# MPR121-Breakout-v12.net
KiCad netlist of a schematic drawn in EAGLE
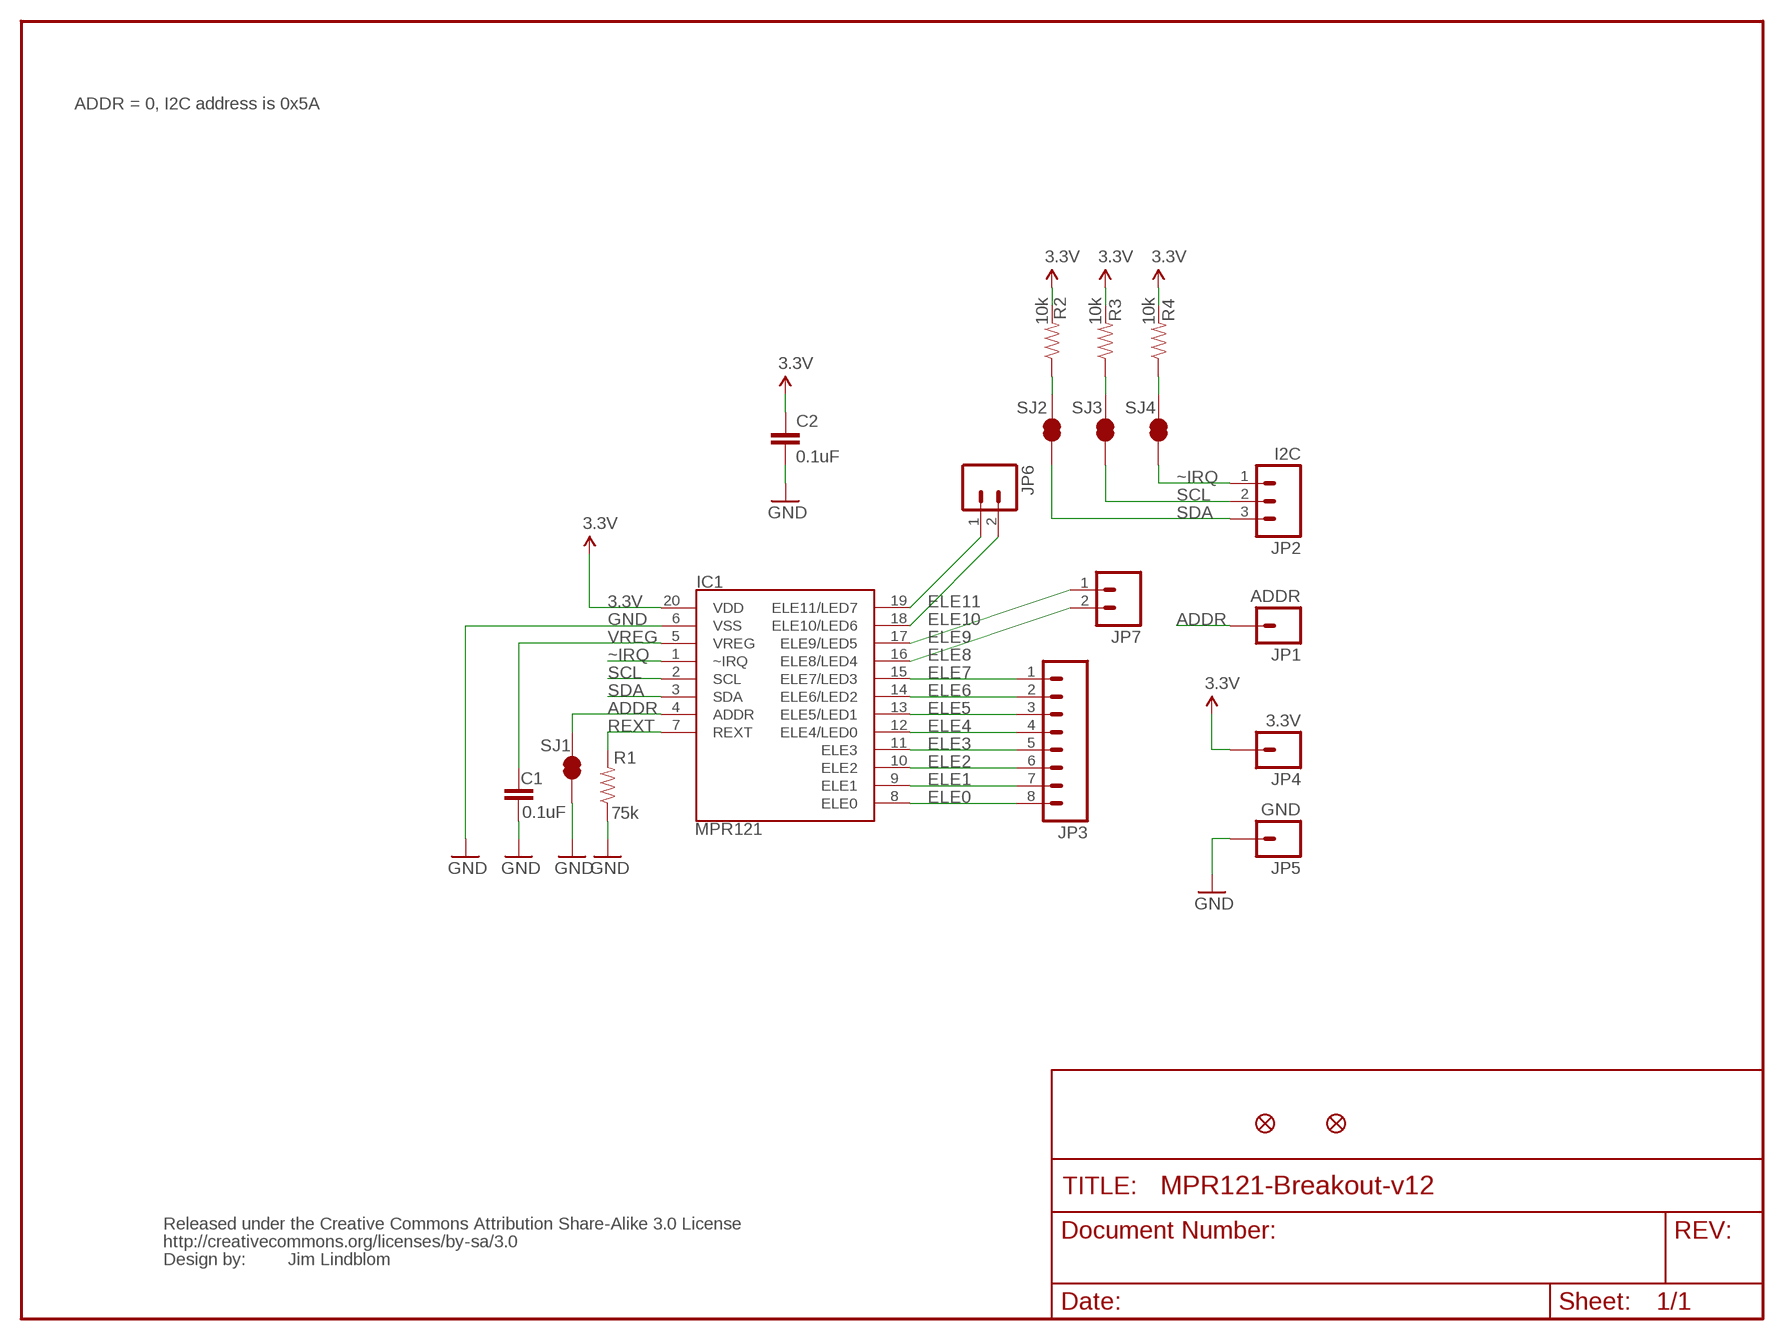
[diagram p0: schematic, sheet 1]

(export (version "E")
  (design (tool "Eeschema 10.0.6"))
  (components
    (comp (ref "C1")
      (value "0.1uF")
      (footprint "eagle-import:0603-CAP")
      (libsource (lib "eagle-import") (part "CAP0603-CAP"))
    )
    (comp (ref "C2")
      (value "0.1uF")
      (footprint "eagle-import:0603-CAP")
      (libsource (lib "eagle-import") (part "CAP0603-CAP"))
    )
    (comp (ref "IC1")
      (value "MPR121")
      (footprint "eagle-import:QFN-20-0.4MM")
      (libsource (lib "eagle-import") (part "MPR121QFN20"))
    )
    (comp (ref "JP1")
      (value "ADDR")
      (footprint "eagle-import:1X01")
      (libsource (lib "eagle-import") (part "M01PTH"))
    )
    (comp (ref "JP2")
      (value "I2C")
      (footprint "eagle-import:1X03")
      (libsource (lib "eagle-import") (part "M03PTH"))
    )
    (comp (ref "JP3")
      (value "M081X08")
      (footprint "eagle-import:1X08")
      (libsource (lib "eagle-import") (part "M081X08"))
    )
    (comp (ref "JP4")
      (value "3.3V")
      (footprint "eagle-import:1X01")
      (libsource (lib "eagle-import") (part "M01PTH"))
    )
    (comp (ref "JP5")
      (value "GND")
      (footprint "eagle-import:1X01")
      (libsource (lib "eagle-import") (part "M01PTH"))
    )
    (comp (ref "JP6")
      (value "M02LOCK")
      (footprint "eagle-import:1X02_LOCK")
      (libsource (lib "eagle-import") (part "M02LOCK"))
    )
    (comp (ref "JP7")
      (value "M02LOCK")
      (footprint "eagle-import:1X02_LOCK")
      (libsource (lib "eagle-import") (part "M02LOCK"))
    )
    (comp (ref "JP8")
      (value "FIDUCIAL1X2")
      (footprint "eagle-import:FIDUCIAL-1X2")
      (libsource (lib "eagle-import") (part "FIDUCIAL1X2"))
    )
    (comp (ref "JP9")
      (value "FIDUCIAL1X2")
      (footprint "eagle-import:FIDUCIAL-1X2")
      (libsource (lib "eagle-import") (part "FIDUCIAL1X2"))
    )
    (comp (ref "R1")
      (value "75k")
      (footprint "eagle-import:0603-RES")
      (libsource (lib "eagle-import") (part "RESISTOR0603-RES"))
    )
    (comp (ref "R2")
      (value "10k")
      (footprint "eagle-import:0603-RES")
      (libsource (lib "eagle-import") (part "RESISTOR0603-RES"))
    )
    (comp (ref "R3")
      (value "10k")
      (footprint "eagle-import:0603-RES")
      (libsource (lib "eagle-import") (part "RESISTOR0603-RES"))
    )
    (comp (ref "R4")
      (value "10k")
      (footprint "eagle-import:0603-RES")
      (libsource (lib "eagle-import") (part "RESISTOR0603-RES"))
    )
    (comp (ref "SJ1")
      (value "SOLDERJUMPERNO")
      (footprint "eagle-import:SJ_2S-NO")
      (libsource (lib "eagle-import") (part "SOLDERJUMPERNO"))
    )
    (comp (ref "SJ2")
      (value "SOLDERJUMPERNO")
      (footprint "eagle-import:SJ_2S-NO")
      (libsource (lib "eagle-import") (part "SOLDERJUMPERNO"))
    )
    (comp (ref "SJ3")
      (value "SOLDERJUMPERNO")
      (footprint "eagle-import:SJ_2S-NO")
      (libsource (lib "eagle-import") (part "SOLDERJUMPERNO"))
    )
    (comp (ref "SJ4")
      (value "SOLDERJUMPERNO")
      (footprint "eagle-import:SJ_2S-NO")
      (libsource (lib "eagle-import") (part "SOLDERJUMPERNO"))
    )
    (comp (ref "U$1")
      (value "CREATIVE_COMMONS")
      (footprint "eagle-import:CREATIVE_COMMONS")
      (libsource (lib "eagle-import") (part "CREATIVE_COMMONS"))
    )
  )
  (nets
    (net (code "1") (name "/ADDR") (class "Default")
      (node (ref "IC1") (pin "4") (pinfunction "ADDR_4") (pintype "bidirectional"))
      (node (ref "JP1") (pin "1") (pinfunction "1_1") (pintype "passive"))
      (node (ref "SJ1") (pin "2") (pinfunction "2_2") (pintype "passive"))
    )
    (net (code "2") (name "/ELE0") (class "Default")
      (node (ref "IC1") (pin "8") (pinfunction "ELE0_8") (pintype "bidirectional"))
      (node (ref "JP3") (pin "8") (pinfunction "8_8") (pintype "passive"))
    )
    (net (code "3") (name "/ELE1") (class "Default")
      (node (ref "IC1") (pin "9") (pinfunction "ELE1_9") (pintype "bidirectional"))
      (node (ref "JP3") (pin "7") (pinfunction "7_7") (pintype "passive"))
    )
    (net (code "4") (name "/ELE2") (class "Default")
      (node (ref "IC1") (pin "10") (pinfunction "ELE2_10") (pintype "bidirectional"))
      (node (ref "JP3") (pin "6") (pinfunction "6_6") (pintype "passive"))
    )
    (net (code "5") (name "/ELE3") (class "Default")
      (node (ref "IC1") (pin "11") (pinfunction "ELE3_11") (pintype "bidirectional"))
      (node (ref "JP3") (pin "5") (pinfunction "5_5") (pintype "passive"))
    )
    (net (code "6") (name "/ELE4") (class "Default")
      (node (ref "IC1") (pin "12") (pinfunction "ELE4/LED0_12") (pintype "bidirectional"))
      (node (ref "JP3") (pin "4") (pinfunction "4_4") (pintype "passive"))
    )
    (net (code "7") (name "/ELE5") (class "Default")
      (node (ref "IC1") (pin "13") (pinfunction "ELE5/LED1_13") (pintype "bidirectional"))
      (node (ref "JP3") (pin "3") (pinfunction "3_3") (pintype "passive"))
    )
    (net (code "8") (name "/ELE6") (class "Default")
      (node (ref "IC1") (pin "14") (pinfunction "ELE6/LED2_14") (pintype "bidirectional"))
      (node (ref "JP3") (pin "2") (pinfunction "2_2") (pintype "passive"))
    )
    (net (code "9") (name "/ELE7") (class "Default")
      (node (ref "IC1") (pin "15") (pinfunction "ELE7/LED3_15") (pintype "bidirectional"))
      (node (ref "JP3") (pin "1") (pinfunction "1_1") (pintype "passive"))
    )
    (net (code "10") (name "/ELE8") (class "Default")
      (node (ref "IC1") (pin "16") (pinfunction "ELE8/LED4_16") (pintype "bidirectional"))
      (node (ref "JP7") (pin "2") (pinfunction "2_2") (pintype "passive"))
    )
    (net (code "11") (name "/ELE9") (class "Default")
      (node (ref "IC1") (pin "17") (pinfunction "ELE9/LED5_17") (pintype "bidirectional"))
      (node (ref "JP7") (pin "1") (pinfunction "1_1") (pintype "passive"))
    )
    (net (code "12") (name "/ELE10") (class "Default")
      (node (ref "IC1") (pin "18") (pinfunction "ELE10/LED6_18") (pintype "bidirectional"))
      (node (ref "JP6") (pin "2") (pinfunction "2_2") (pintype "passive"))
    )
    (net (code "13") (name "/ELE11") (class "Default")
      (node (ref "IC1") (pin "19") (pinfunction "ELE11/LED7_19") (pintype "bidirectional"))
      (node (ref "JP6") (pin "1") (pinfunction "1_1") (pintype "passive"))
    )
    (net (code "14") (name "/REXT") (class "Default")
      (node (ref "IC1") (pin "7") (pinfunction "REXT_7") (pintype "bidirectional"))
      (node (ref "R1") (pin "2") (pinfunction "2_2") (pintype "passive"))
    )
    (net (code "15") (name "/SCL") (class "Default")
      (node (ref "IC1") (pin "2") (pinfunction "SCL_2") (pintype "bidirectional"))
      (node (ref "JP2") (pin "2") (pinfunction "2_2") (pintype "passive"))
      (node (ref "SJ3") (pin "1") (pinfunction "1_1") (pintype "passive"))
    )
    (net (code "16") (name "/SDA") (class "Default")
      (node (ref "IC1") (pin "3") (pinfunction "SDA_3") (pintype "bidirectional"))
      (node (ref "JP2") (pin "3") (pinfunction "3_3") (pintype "passive"))
      (node (ref "SJ2") (pin "1") (pinfunction "1_1") (pintype "passive"))
    )
    (net (code "17") (name "/VREG") (class "Default")
      (node (ref "C1") (pin "1") (pinfunction "1_1") (pintype "passive"))
      (node (ref "IC1") (pin "5") (pinfunction "VREG_5") (pintype "bidirectional"))
    )
    (net (code "18") (name "/~{IRQ}") (class "Default")
      (node (ref "IC1") (pin "1") (pinfunction "~{IRQ}_1") (pintype "bidirectional"))
      (node (ref "JP2") (pin "1") (pinfunction "1_1") (pintype "passive"))
      (node (ref "SJ4") (pin "1") (pinfunction "1_1") (pintype "passive"))
    )
    (net (code "19") (name "3.3V") (class "Default")
      (node (ref "C2") (pin "1") (pinfunction "1_1") (pintype "passive"))
      (node (ref "IC1") (pin "20") (pinfunction "VDD_20") (pintype "bidirectional"))
      (node (ref "JP4") (pin "1") (pinfunction "1_1") (pintype "passive"))
      (node (ref "R2") (pin "2") (pinfunction "2_2") (pintype "passive"))
      (node (ref "R3") (pin "2") (pinfunction "2_2") (pintype "passive"))
      (node (ref "R4") (pin "2") (pinfunction "2_2") (pintype "passive"))
    )
    (net (code "20") (name "GND") (class "Default")
      (node (ref "C1") (pin "2") (pinfunction "2_2") (pintype "passive"))
      (node (ref "C2") (pin "2") (pinfunction "2_2") (pintype "passive"))
      (node (ref "IC1") (pin "6") (pinfunction "VSS_6") (pintype "bidirectional"))
      (node (ref "JP5") (pin "1") (pinfunction "1_1") (pintype "passive"))
      (node (ref "R1") (pin "1") (pinfunction "1_1") (pintype "passive"))
      (node (ref "SJ1") (pin "1") (pinfunction "1_1") (pintype "passive"))
    )
    (net (code "21") (name "Net-(R2-Pad1)") (class "Default")
      (node (ref "R2") (pin "1") (pinfunction "1_1") (pintype "passive"))
      (node (ref "SJ2") (pin "2") (pinfunction "2_2") (pintype "passive"))
    )
    (net (code "22") (name "Net-(R3-Pad1)") (class "Default")
      (node (ref "R3") (pin "1") (pinfunction "1_1") (pintype "passive"))
      (node (ref "SJ3") (pin "2") (pinfunction "2_2") (pintype "passive"))
    )
    (net (code "23") (name "Net-(R4-Pad1)") (class "Default")
      (node (ref "R4") (pin "1") (pinfunction "1_1") (pintype "passive"))
      (node (ref "SJ4") (pin "2") (pinfunction "2_2") (pintype "passive"))
    )
  )
)
